# iot_pcb.net
KiCad netlist of a schematic drawn in EAGLE
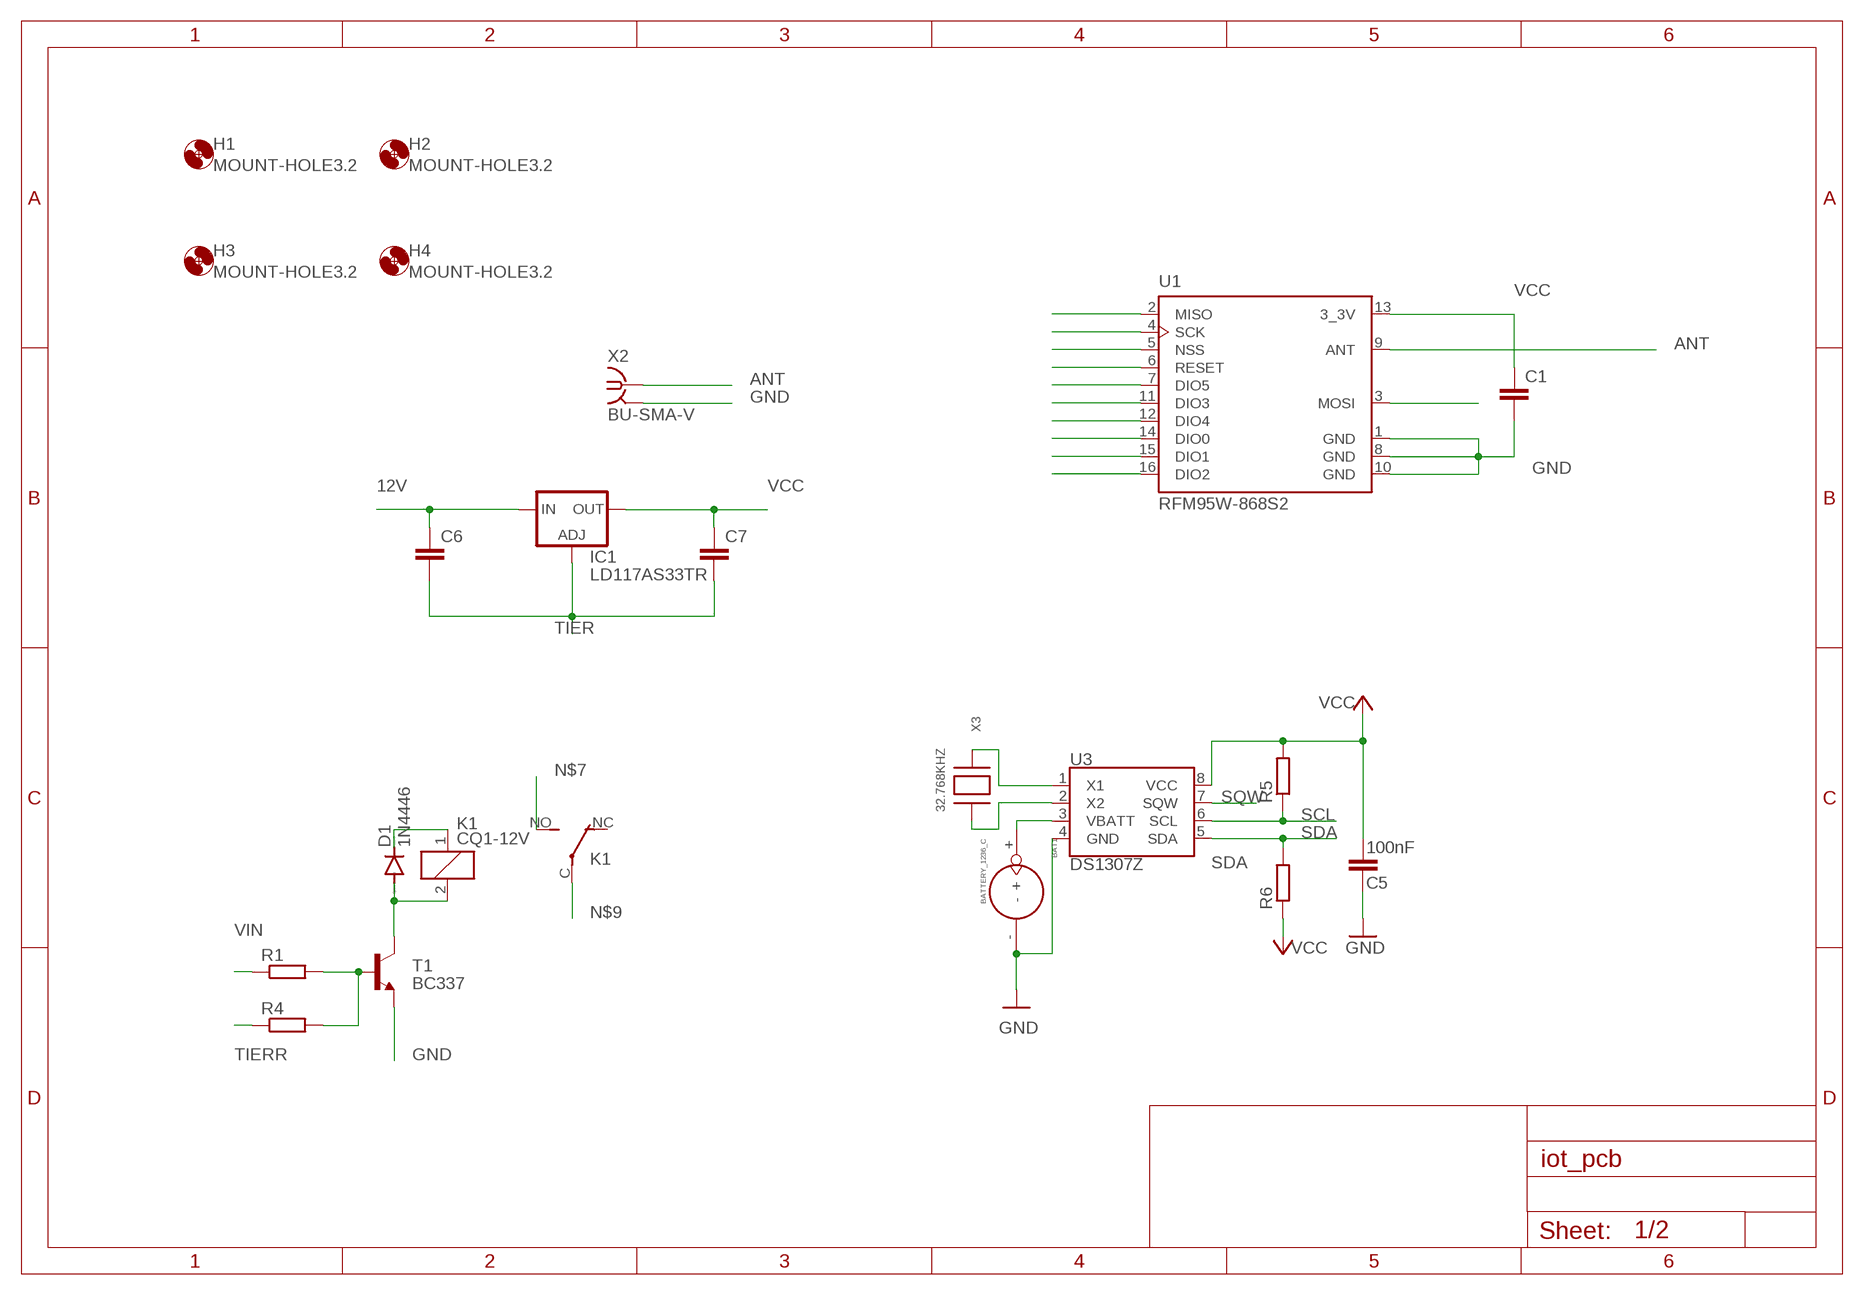
[diagram p0: schematic, sheet 1]
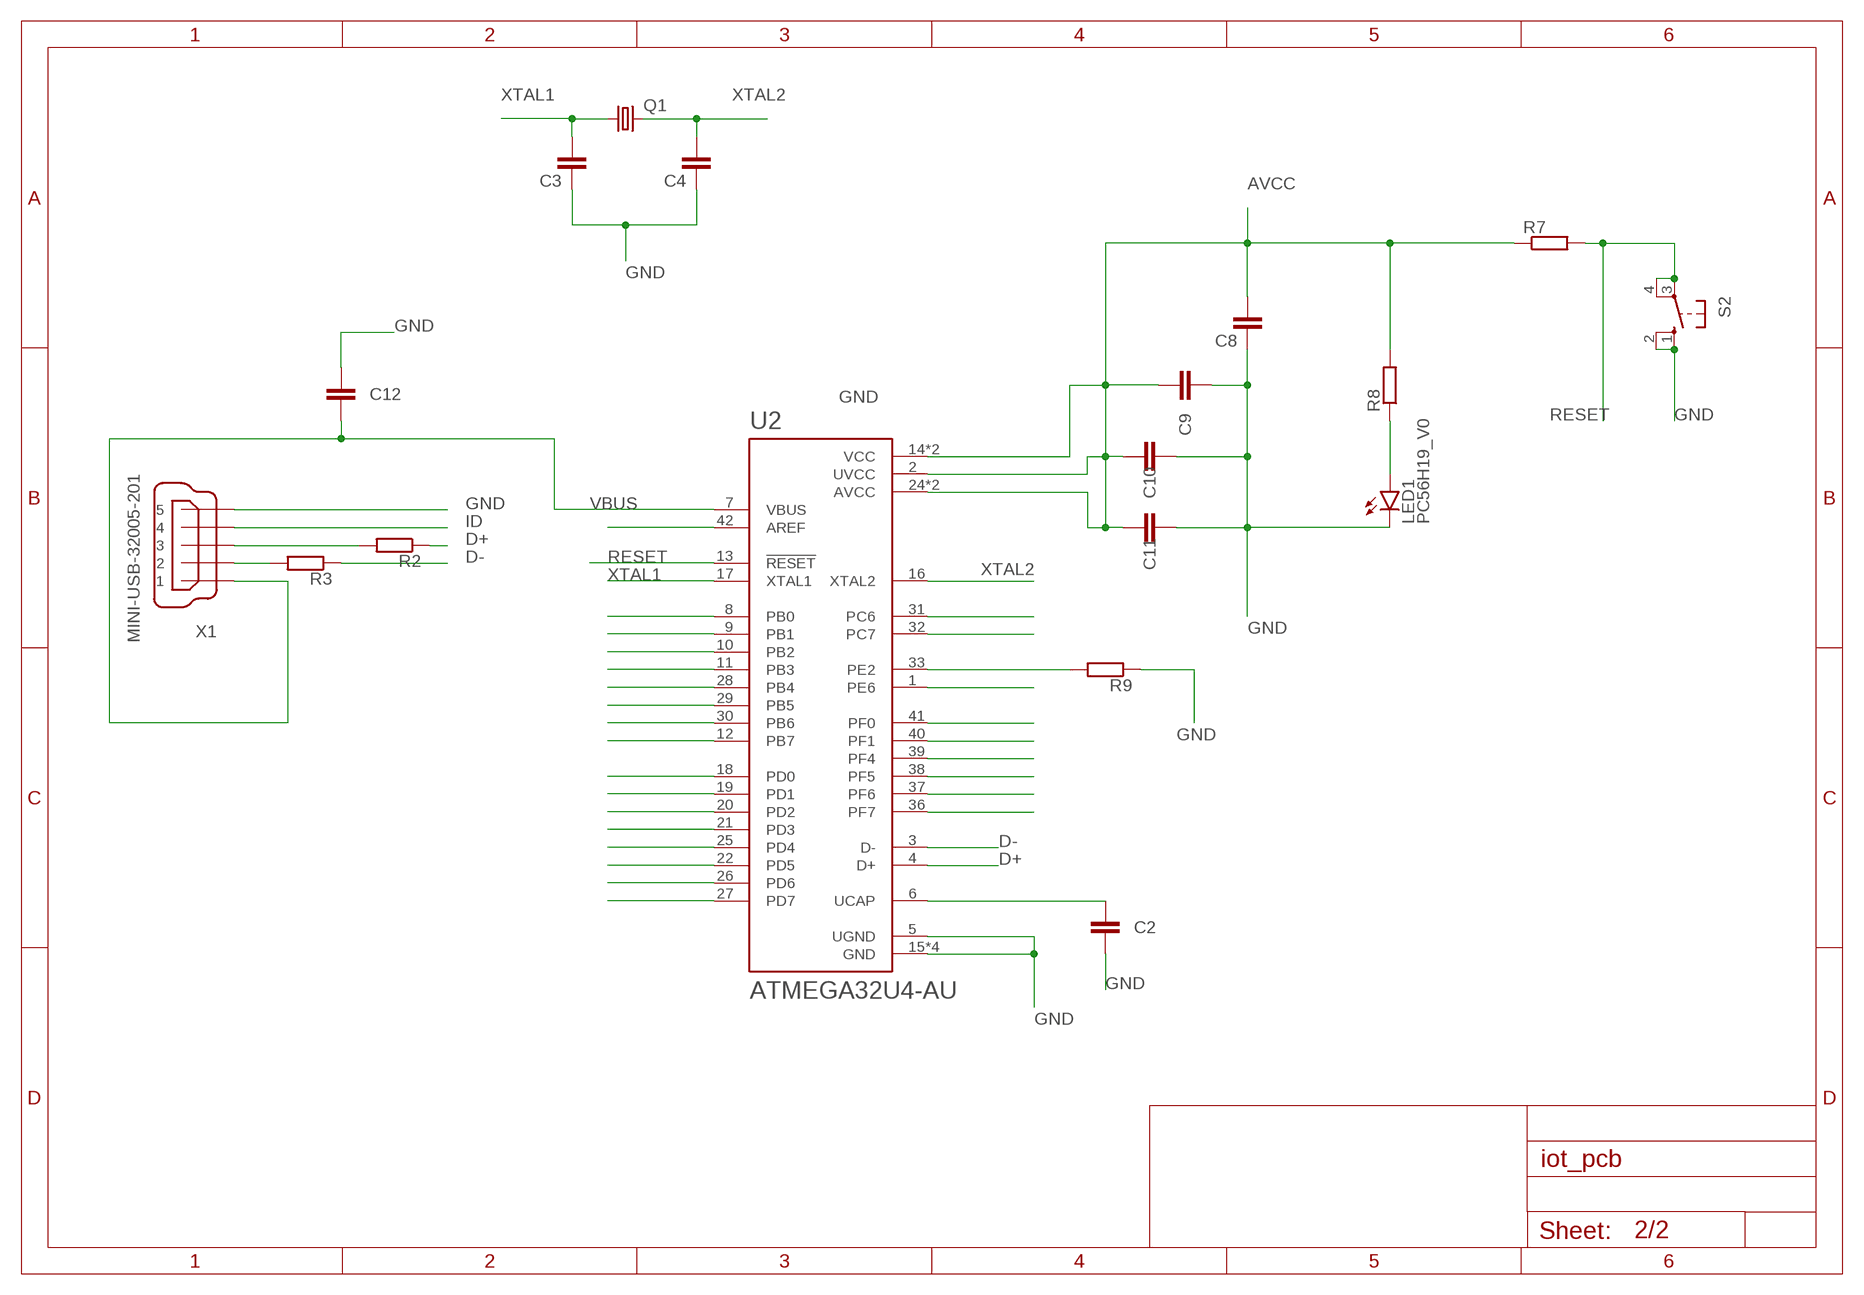
[diagram p1: schematic, sheet 2]

(export (version "E")
  (design (tool "Eeschema 10.0.6"))
  (components
    (comp (ref "BAT1")
      (value "BATTERY_1236_C")
      (footprint "eagle-import:BATTERY_1236_C")
      (libsource (lib "eagle-import") (part "BATTERY_1236_C"))
    )
    (comp (ref "C1")
      (value "C-EU050-025X075")
      (footprint "eagle-import:C050-025X075")
      (libsource (lib "eagle-import") (part "rcl_334_C-EU050-025X075"))
    )
    (comp (ref "C5")
      (value "100nF")
      (footprint "eagle-import:C0603")
      (libsource (lib "eagle-import") (part "C-EUC0603"))
    )
    (comp (ref "C6")
      (value "C-EU050-025X075")
      (footprint "eagle-import:C050-025X075")
      (libsource (lib "eagle-import") (part "rcl_334_C-EU050-025X075"))
    )
    (comp (ref "C7")
      (value "C-EU050-025X075")
      (footprint "eagle-import:C050-025X075")
      (libsource (lib "eagle-import") (part "rcl_334_C-EU050-025X075"))
    )
    (comp (ref "D1")
      (value "1N4446")
      (footprint "eagle-import:DO35-10")
      (libsource (lib "eagle-import") (part "1N4446"))
    )
    (comp (ref "H1")
      (value "MOUNT-HOLE3.2")
      (footprint "eagle-import:3,2")
      (libsource (lib "eagle-import") (part "MOUNT-HOLE3.2"))
    )
    (comp (ref "H2")
      (value "MOUNT-HOLE3.2")
      (footprint "eagle-import:3,2")
      (libsource (lib "eagle-import") (part "MOUNT-HOLE3.2"))
    )
    (comp (ref "H3")
      (value "MOUNT-HOLE3.2")
      (footprint "eagle-import:3,2")
      (libsource (lib "eagle-import") (part "MOUNT-HOLE3.2"))
    )
    (comp (ref "H4")
      (value "MOUNT-HOLE3.2")
      (footprint "eagle-import:3,2")
      (libsource (lib "eagle-import") (part "MOUNT-HOLE3.2"))
    )
    (comp (ref "IC1")
      (value "LD117AS33TR")
      (footprint "eagle-import:SOT223")
      (libsource (lib "eagle-import") (part "LD117A?S33TR"))
    )
    (comp (ref "K1")
      (value "CQ1-12V")
      (footprint "eagle-import:CQ1")
      (libsource (lib "eagle-import") (part "CQ1-12V"))
    )
    (comp (ref "R1")
      (value "R-EU_0207/10")
      (footprint "eagle-import:0207_10")
      (libsource (lib "eagle-import") (part "R-EU_0207/10"))
    )
    (comp (ref "R4")
      (value "R-EU_0207/10")
      (footprint "eagle-import:0207_10")
      (libsource (lib "eagle-import") (part "R-EU_0207/10"))
    )
    (comp (ref "R5")
      (value "R-EU_0207/10")
      (footprint "eagle-import:0207_10")
      (libsource (lib "eagle-import") (part "R-EU_0207/10"))
    )
    (comp (ref "R6")
      (value "R-EU_0207/10")
      (footprint "eagle-import:0207_10")
      (libsource (lib "eagle-import") (part "R-EU_0207/10"))
    )
    (comp (ref "T1")
      (value "BC337")
      (footprint "eagle-import:TO92")
      (libsource (lib "eagle-import") (part "BC337"))
    )
    (comp (ref "U1")
      (value "RFM95W-868S2")
      (footprint "eagle-import:XCVR_RFM95W-868S2")
      (fields (field (name "MF") "RF"))
      (libsource (lib "eagle-import") (part "RFM95W-868S2"))
    )
    (comp (ref "U3")
      (value "DS1307Z")
      (footprint "eagle-import:SO08-0.15")
      (libsource (lib "eagle-import") (part "DS1307Z"))
    )
    (comp (ref "X2")
      (value "BU-SMA-V")
      (footprint "eagle-import:BU-SMA-V")
      (libsource (lib "eagle-import") (part "BU-SMA-V"))
    )
    (comp (ref "X3")
      (value "32.768KHZ")
      (footprint "eagle-import:XTAL3215")
      (libsource (lib "eagle-import") (part "XTAL-3.2X1.5"))
    )
    (comp (ref "C2")
      (value "C-EU050-025X075")
      (footprint "eagle-import:C050-025X075")
      (libsource (lib "eagle-import") (part "rcl_334_C-EU050-025X075"))
    )
    (comp (ref "C3")
      (value "C-EU050-025X075")
      (footprint "eagle-import:C050-025X075")
      (libsource (lib "eagle-import") (part "rcl_334_C-EU050-025X075"))
    )
    (comp (ref "C4")
      (value "C-EU050-025X075")
      (footprint "eagle-import:C050-025X075")
      (libsource (lib "eagle-import") (part "rcl_334_C-EU050-025X075"))
    )
    (comp (ref "C8")
      (value "C-EU050-025X075")
      (footprint "eagle-import:C050-025X075")
      (libsource (lib "eagle-import") (part "rcl_334_C-EU050-025X075"))
    )
    (comp (ref "C9")
      (value "C-EU050-025X075")
      (footprint "eagle-import:C050-025X075")
      (libsource (lib "eagle-import") (part "rcl_334_C-EU050-025X075"))
    )
    (comp (ref "C10")
      (value "C-EU050-025X075")
      (footprint "eagle-import:C050-025X075")
      (libsource (lib "eagle-import") (part "rcl_334_C-EU050-025X075"))
    )
    (comp (ref "C11")
      (value "C-EU050-025X075")
      (footprint "eagle-import:C050-025X075")
      (libsource (lib "eagle-import") (part "rcl_334_C-EU050-025X075"))
    )
    (comp (ref "C12")
      (value "C-EU050-025X075")
      (footprint "eagle-import:C050-025X075")
      (libsource (lib "eagle-import") (part "rcl_334_C-EU050-025X075"))
    )
    (comp (ref "LED1")
      (value "PC56H19_V0")
      (footprint "eagle-import:PC56H19_V0")
      (libsource (lib "eagle-import") (part "PC56H19_V0"))
    )
    (comp (ref "Q1")
      (value "CRYSTALHC49S")
      (footprint "eagle-import:HC49_S")
      (libsource (lib "eagle-import") (part "CRYSTALHC49S"))
    )
    (comp (ref "R2")
      (value "R-EU_0204/7")
      (footprint "eagle-import:0204_7")
      (libsource (lib "eagle-import") (part "R-EU_0204/7"))
    )
    (comp (ref "R3")
      (value "R-EU_0204/7")
      (footprint "eagle-import:0204_7")
      (libsource (lib "eagle-import") (part "R-EU_0204/7"))
    )
    (comp (ref "R7")
      (value "R-EU_0204/7")
      (footprint "eagle-import:0204_7")
      (libsource (lib "eagle-import") (part "R-EU_0204/7"))
    )
    (comp (ref "R8")
      (value "R-EU_0204/7")
      (footprint "eagle-import:0204_7")
      (libsource (lib "eagle-import") (part "R-EU_0204/7"))
    )
    (comp (ref "R9")
      (value "R-EU_0204/7")
      (footprint "eagle-import:0204_7")
      (libsource (lib "eagle-import") (part "R-EU_0204/7"))
    )
    (comp (ref "S2")
      (value "40-XX")
      (footprint "eagle-import:B3F-40XX")
      (fields (field (name "MF") "OMRON COMPONENTS USA") (field (name "MPN") "B3F-4000"))
      (libsource (lib "eagle-import") (part "40-XX"))
    )
    (comp (ref "U2")
      (value "ATMEGA32U4-AU")
      (footprint "eagle-import:QFP80P1200X1200X120-44N")
      (fields (field (name "MF") "Rochester Electronics, LLC"))
      (libsource (lib "eagle-import") (part "ATMEGA32U4-AU"))
    )
    (comp (ref "X1")
      (value "MINI-USB-32005-201")
      (footprint "eagle-import:32005-201")
      (libsource (lib "eagle-import") (part "MINI-USB-32005-201"))
    )
  )
  (nets
    (net (code "1") (name "12V") (class "Default")
      (node (ref "C6") (pin "1") (pinfunction "1_1") (pintype "passive"))
      (node (ref "IC1") (pin "3") (pinfunction "IN_3") (pintype "input"))
    )
    (net (code "2") (name "ANT") (class "Default")
      (node (ref "U1") (pin "9") (pinfunction "ANT_9") (pintype "passive"))
      (node (ref "X2") (pin "1") (pinfunction "1_1") (pintype "passive"))
    )
    (net (code "3") (name "AVCC") (class "Default")
      (node (ref "C10") (pin "2") (pinfunction "2_2") (pintype "passive"))
      (node (ref "C11") (pin "1") (pinfunction "1_1") (pintype "passive"))
      (node (ref "C8") (pin "2") (pinfunction "2_2") (pintype "passive"))
      (node (ref "C9") (pin "2") (pinfunction "2_2") (pintype "passive"))
      (node (ref "R7") (pin "1") (pinfunction "1_1") (pintype "passive"))
      (node (ref "R8") (pin "2") (pinfunction "2_2") (pintype "passive"))
      (node (ref "U2") (pin "14") (pinfunction "VCC_14") (pintype "power_in"))
      (node (ref "U2") (pin "2") (pinfunction "UVCC_2") (pintype "power_in"))
      (node (ref "U2") (pin "24") (pinfunction "AVCC_24") (pintype "power_in"))
      (node (ref "U2") (pin "34") (pinfunction "VCC_34") (pintype "power_in"))
      (node (ref "U2") (pin "44") (pinfunction "AVCC_44") (pintype "power_in"))
    )
    (net (code "4") (name "D+") (class "Default")
      (node (ref "R2") (pin "1") (pinfunction "1_1") (pintype "passive"))
      (node (ref "U2") (pin "4") (pinfunction "D+_4") (pintype "bidirectional"))
    )
    (net (code "5") (name "D-") (class "Default")
      (node (ref "R3") (pin "1") (pinfunction "1_1") (pintype "passive"))
      (node (ref "U2") (pin "3") (pinfunction "D-_3") (pintype "bidirectional"))
    )
    (net (code "6") (name "GND") (class "Default")
      (node (ref "BAT1") (pin "-") (pinfunction "-_-") (pintype "bidirectional"))
      (node (ref "C1") (pin "2") (pinfunction "2_2") (pintype "passive"))
      (node (ref "C10") (pin "1") (pinfunction "1_1") (pintype "passive"))
      (node (ref "C11") (pin "2") (pinfunction "2_2") (pintype "passive"))
      (node (ref "C12") (pin "1") (pinfunction "1_1") (pintype "passive"))
      (node (ref "C2") (pin "2") (pinfunction "2_2") (pintype "passive"))
      (node (ref "C3") (pin "1") (pinfunction "1_1") (pintype "passive"))
      (node (ref "C4") (pin "1") (pinfunction "1_1") (pintype "passive"))
      (node (ref "C5") (pin "1") (pinfunction "1_1") (pintype "passive"))
      (node (ref "C8") (pin "1") (pinfunction "1_1") (pintype "passive"))
      (node (ref "C9") (pin "1") (pinfunction "1_1") (pintype "passive"))
      (node (ref "LED1") (pin "1") (pinfunction "C_1") (pintype "passive"))
      (node (ref "LED1") (pin "3") (pinfunction "C_3") (pintype "passive"))
      (node (ref "R9") (pin "1") (pinfunction "1_1") (pintype "passive"))
      (node (ref "S2") (pin "1") (pinfunction "S_1") (pintype "passive"))
      (node (ref "S2") (pin "2") (pinfunction "S1_2") (pintype "passive"))
      (node (ref "T1") (pin "1") (pinfunction "E_1") (pintype "passive"))
      (node (ref "U1") (pin "1") (pinfunction "GND_1") (pintype "power_in"))
      (node (ref "U1") (pin "10") (pinfunction "GND_10") (pintype "power_in"))
      (node (ref "U1") (pin "8") (pinfunction "GND_8") (pintype "power_in"))
      (node (ref "U2") (pin "15") (pinfunction "GND_15") (pintype "power_in"))
      (node (ref "U2") (pin "23") (pinfunction "GND_23") (pintype "power_in"))
      (node (ref "U2") (pin "35") (pinfunction "GND_35") (pintype "power_in"))
      (node (ref "U2") (pin "43") (pinfunction "GND_43") (pintype "power_in"))
      (node (ref "U2") (pin "5") (pinfunction "UGND_5") (pintype "power_in"))
      (node (ref "U3") (pin "4") (pinfunction "GND_4") (pintype "bidirectional"))
      (node (ref "X1") (pin "5") (pinfunction "5_5") (pintype "passive"))
      (node (ref "X2") (pin "2") (pinfunction "2_2") (pintype "passive"))
      (node (ref "X2") (pin "3") (pinfunction "2_3") (pintype "passive"))
      (node (ref "X2") (pin "4") (pinfunction "2_4") (pintype "passive"))
      (node (ref "X2") (pin "5") (pinfunction "2_5") (pintype "passive"))
    )
    (net (code "7") (name "ID") (class "Default")
      (node (ref "X1") (pin "4") (pinfunction "4_4") (pintype "passive"))
    )
    (net (code "8") (name "N$7") (class "Default")
      (node (ref "K1") (pin "NO") (pinfunction "S_NO") (pintype "passive"))
      (node (ref "U2") (pin "10") (pinfunction "PB2_10") (pintype "bidirectional"))
    )
    (net (code "9") (name "N$9") (class "Default")
      (node (ref "K1") (pin "C") (pinfunction "P_C") (pintype "passive"))
      (node (ref "U2") (pin "28") (pinfunction "PB4_28") (pintype "bidirectional"))
    )
    (net (code "10") (name "Net-(D1-PadC)") (class "Default")
      (node (ref "D1") (pin "C") (pinfunction "C_C") (pintype "passive"))
      (node (ref "K1") (pin "1") (pinfunction "1_1") (pintype "passive"))
    )
    (net (code "11") (name "Net-(LED1-A-Pad2)") (class "Default")
      (node (ref "LED1") (pin "2") (pinfunction "A_2") (pintype "passive"))
      (node (ref "LED1") (pin "4") (pinfunction "A_4") (pintype "passive"))
      (node (ref "R8") (pin "1") (pinfunction "1_1") (pintype "passive"))
    )
    (net (code "12") (name "Net-(R2-Pad2)") (class "Default")
      (node (ref "R2") (pin "2") (pinfunction "2_2") (pintype "passive"))
      (node (ref "X1") (pin "3") (pinfunction "3_3") (pintype "passive"))
    )
    (net (code "13") (name "Net-(R3-Pad2)") (class "Default")
      (node (ref "R3") (pin "2") (pinfunction "2_2") (pintype "passive"))
      (node (ref "X1") (pin "2") (pinfunction "2_2") (pintype "passive"))
    )
    (net (code "14") (name "Net-(T1-B)") (class "Default")
      (node (ref "R1") (pin "2") (pinfunction "2_2") (pintype "passive"))
      (node (ref "R4") (pin "2") (pinfunction "2_2") (pintype "passive"))
      (node (ref "T1") (pin "2") (pinfunction "B_2") (pintype "passive"))
    )
    (net (code "15") (name "Net-(T1-C)") (class "Default")
      (node (ref "D1") (pin "A") (pinfunction "A_A") (pintype "passive"))
      (node (ref "K1") (pin "2") (pinfunction "2_2") (pintype "passive"))
      (node (ref "T1") (pin "3") (pinfunction "C_3") (pintype "passive"))
    )
    (net (code "16") (name "Net-(U2-PE2)") (class "Default")
      (node (ref "R9") (pin "2") (pinfunction "2_2") (pintype "passive"))
      (node (ref "U2") (pin "33") (pinfunction "PE2_33") (pintype "bidirectional"))
    )
    (net (code "17") (name "Net-(U2-UCAP)") (class "Default")
      (node (ref "C2") (pin "1") (pinfunction "1_1") (pintype "passive"))
      (node (ref "U2") (pin "6") (pinfunction "UCAP_6") (pintype "passive"))
    )
    (net (code "18") (name "Net-(U3-VBATT)") (class "Default")
      (node (ref "BAT1") (pin "+") (pinfunction "+_+") (pintype "bidirectional"))
      (node (ref "U3") (pin "3") (pinfunction "VBATT_3") (pintype "bidirectional"))
    )
    (net (code "19") (name "Net-(U3-X1)") (class "Default")
      (node (ref "U3") (pin "1") (pinfunction "X1_1") (pintype "bidirectional"))
      (node (ref "X3") (pin "P$2") (pinfunction "P$2_P$2") (pintype "bidirectional"))
    )
    (net (code "20") (name "Net-(U3-X2)") (class "Default")
      (node (ref "U3") (pin "2") (pinfunction "X2_2") (pintype "bidirectional"))
      (node (ref "X3") (pin "P$1") (pinfunction "P$1_P$1") (pintype "bidirectional"))
    )
    (net (code "21") (name "RESET") (class "Default")
      (node (ref "R7") (pin "2") (pinfunction "2_2") (pintype "passive"))
      (node (ref "S2") (pin "3") (pinfunction "P_3") (pintype "passive"))
      (node (ref "S2") (pin "4") (pinfunction "P1_4") (pintype "passive"))
      (node (ref "U2") (pin "13") (pinfunction "~{RESET}_13") (pintype "input"))
    )
    (net (code "22") (name "SCL") (class "Default")
      (node (ref "R5") (pin "1") (pinfunction "1_1") (pintype "passive"))
      (node (ref "U3") (pin "6") (pinfunction "SCL_6") (pintype "bidirectional"))
    )
    (net (code "23") (name "SDA") (class "Default")
      (node (ref "R6") (pin "2") (pinfunction "2_2") (pintype "passive"))
      (node (ref "U3") (pin "5") (pinfunction "SDA_5") (pintype "bidirectional"))
    )
    (net (code "24") (name "SQW") (class "Default")
      (node (ref "U3") (pin "7") (pinfunction "SQW_7") (pintype "bidirectional"))
    )
    (net (code "25") (name "TIER") (class "Default")
      (node (ref "C6") (pin "2") (pinfunction "2_2") (pintype "passive"))
      (node (ref "C7") (pin "2") (pinfunction "2_2") (pintype "passive"))
      (node (ref "IC1") (pin "1") (pinfunction "ADJ_1") (pintype "input"))
    )
    (net (code "26") (name "TIERR") (class "Default")
      (node (ref "R4") (pin "1") (pinfunction "1_1") (pintype "passive"))
    )
    (net (code "27") (name "VBUS") (class "Default")
      (node (ref "C12") (pin "2") (pinfunction "2_2") (pintype "passive"))
      (node (ref "U2") (pin "7") (pinfunction "VBUS_7") (pintype "input"))
      (node (ref "X1") (pin "1") (pinfunction "1_1") (pintype "passive"))
    )
    (net (code "28") (name "VCC") (class "Default")
      (node (ref "C1") (pin "1") (pinfunction "1_1") (pintype "passive"))
      (node (ref "C5") (pin "2") (pinfunction "2_2") (pintype "passive"))
      (node (ref "C7") (pin "1") (pinfunction "1_1") (pintype "passive"))
      (node (ref "IC1") (pin "4") (pinfunction "OUT_4") (pintype "passive"))
      (node (ref "R5") (pin "2") (pinfunction "2_2") (pintype "passive"))
      (node (ref "R6") (pin "1") (pinfunction "1_1") (pintype "passive"))
      (node (ref "U1") (pin "13") (pinfunction "3_3V_13") (pintype "power_in"))
      (node (ref "U3") (pin "8") (pinfunction "VCC_8") (pintype "bidirectional"))
    )
    (net (code "29") (name "VIN") (class "Default")
      (node (ref "R1") (pin "1") (pinfunction "1_1") (pintype "passive"))
    )
    (net (code "30") (name "XTAL1") (class "Default")
      (node (ref "C3") (pin "2") (pinfunction "2_2") (pintype "passive"))
      (node (ref "Q1") (pin "1") (pinfunction "1_1") (pintype "passive"))
      (node (ref "U2") (pin "17") (pinfunction "XTAL1_17") (pintype "input"))
    )
    (net (code "31") (name "XTAL2") (class "Default")
      (node (ref "C4") (pin "2") (pinfunction "2_2") (pintype "passive"))
      (node (ref "Q1") (pin "2") (pinfunction "2_2") (pintype "passive"))
      (node (ref "U2") (pin "16") (pinfunction "XTAL2_16") (pintype "output"))
    )
    (net (code "32") (name "unconnected-(K1B-O-PadNC)") (class "Default")
      (node (ref "K1") (pin "NC") (pinfunction "O_NC") (pintype "passive"))
    )
    (net (code "33") (name "unconnected-(U1-DIO0-Pad14)") (class "Default")
      (node (ref "U1") (pin "14") (pinfunction "DIO0_14") (pintype "bidirectional"))
    )
    (net (code "34") (name "unconnected-(U1-DIO1-Pad15)") (class "Default")
      (node (ref "U1") (pin "15") (pinfunction "DIO1_15") (pintype "bidirectional"))
    )
    (net (code "35") (name "unconnected-(U1-DIO2-Pad16)") (class "Default")
      (node (ref "U1") (pin "16") (pinfunction "DIO2_16") (pintype "bidirectional"))
    )
    (net (code "36") (name "unconnected-(U1-DIO3-Pad11)") (class "Default")
      (node (ref "U1") (pin "11") (pinfunction "DIO3_11") (pintype "bidirectional"))
    )
    (net (code "37") (name "unconnected-(U1-DIO4-Pad12)") (class "Default")
      (node (ref "U1") (pin "12") (pinfunction "DIO4_12") (pintype "bidirectional"))
    )
    (net (code "38") (name "unconnected-(U1-DIO5-Pad7)") (class "Default")
      (node (ref "U1") (pin "7") (pinfunction "DIO5_7") (pintype "bidirectional"))
    )
    (net (code "39") (name "unconnected-(U1-MISO-Pad2)") (class "Default")
      (node (ref "U1") (pin "2") (pinfunction "MISO_2") (pintype "input"))
    )
    (net (code "40") (name "unconnected-(U1-MOSI-Pad3)") (class "Default")
      (node (ref "U1") (pin "3") (pinfunction "MOSI_3") (pintype "output"))
    )
    (net (code "41") (name "unconnected-(U1-NSS-Pad5)") (class "Default")
      (node (ref "U1") (pin "5") (pinfunction "NSS_5") (pintype "input"))
    )
    (net (code "42") (name "unconnected-(U1-RESET-Pad6)") (class "Default")
      (node (ref "U1") (pin "6") (pinfunction "RESET_6") (pintype "bidirectional"))
    )
    (net (code "43") (name "unconnected-(U1-SCK-Pad4)") (class "Default")
      (node (ref "U1") (pin "4") (pinfunction "SCK_4") (pintype "input"))
    )
    (net (code "44") (name "unconnected-(U2-AREF-Pad42)") (class "Default")
      (node (ref "U2") (pin "42") (pinfunction "AREF_42") (pintype "input"))
    )
    (net (code "45") (name "unconnected-(U2-PB0-Pad8)") (class "Default")
      (node (ref "U2") (pin "8") (pinfunction "PB0_8") (pintype "bidirectional"))
    )
    (net (code "46") (name "unconnected-(U2-PB1-Pad9)") (class "Default")
      (node (ref "U2") (pin "9") (pinfunction "PB1_9") (pintype "bidirectional"))
    )
    (net (code "47") (name "unconnected-(U2-PB3-Pad11)") (class "Default")
      (node (ref "U2") (pin "11") (pinfunction "PB3_11") (pintype "bidirectional"))
    )
    (net (code "48") (name "unconnected-(U2-PB5-Pad29)") (class "Default")
      (node (ref "U2") (pin "29") (pinfunction "PB5_29") (pintype "bidirectional"))
    )
    (net (code "49") (name "unconnected-(U2-PB6-Pad30)") (class "Default")
      (node (ref "U2") (pin "30") (pinfunction "PB6_30") (pintype "bidirectional"))
    )
    (net (code "50") (name "unconnected-(U2-PB7-Pad12)") (class "Default")
      (node (ref "U2") (pin "12") (pinfunction "PB7_12") (pintype "bidirectional"))
    )
    (net (code "51") (name "unconnected-(U2-PC6-Pad31)") (class "Default")
      (node (ref "U2") (pin "31") (pinfunction "PC6_31") (pintype "bidirectional"))
    )
    (net (code "52") (name "unconnected-(U2-PC7-Pad32)") (class "Default")
      (node (ref "U2") (pin "32") (pinfunction "PC7_32") (pintype "bidirectional"))
    )
    (net (code "53") (name "unconnected-(U2-PD0-Pad18)") (class "Default")
      (node (ref "U2") (pin "18") (pinfunction "PD0_18") (pintype "bidirectional"))
    )
    (net (code "54") (name "unconnected-(U2-PD1-Pad19)") (class "Default")
      (node (ref "U2") (pin "19") (pinfunction "PD1_19") (pintype "bidirectional"))
    )
    (net (code "55") (name "unconnected-(U2-PD2-Pad20)") (class "Default")
      (node (ref "U2") (pin "20") (pinfunction "PD2_20") (pintype "bidirectional"))
    )
    (net (code "56") (name "unconnected-(U2-PD3-Pad21)") (class "Default")
      (node (ref "U2") (pin "21") (pinfunction "PD3_21") (pintype "bidirectional"))
    )
    (net (code "57") (name "unconnected-(U2-PD4-Pad25)") (class "Default")
      (node (ref "U2") (pin "25") (pinfunction "PD4_25") (pintype "bidirectional"))
    )
    (net (code "58") (name "unconnected-(U2-PD5-Pad22)") (class "Default")
      (node (ref "U2") (pin "22") (pinfunction "PD5_22") (pintype "bidirectional"))
    )
    (net (code "59") (name "unconnected-(U2-PD6-Pad26)") (class "Default")
      (node (ref "U2") (pin "26") (pinfunction "PD6_26") (pintype "bidirectional"))
    )
    (net (code "60") (name "unconnected-(U2-PD7-Pad27)") (class "Default")
      (node (ref "U2") (pin "27") (pinfunction "PD7_27") (pintype "bidirectional"))
    )
    (net (code "61") (name "unconnected-(U2-PE6-Pad1)") (class "Default")
      (node (ref "U2") (pin "1") (pinfunction "PE6_1") (pintype "bidirectional"))
    )
    (net (code "62") (name "unconnected-(U2-PF0-Pad41)") (class "Default")
      (node (ref "U2") (pin "41") (pinfunction "PF0_41") (pintype "bidirectional"))
    )
    (net (code "63") (name "unconnected-(U2-PF1-Pad40)") (class "Default")
      (node (ref "U2") (pin "40") (pinfunction "PF1_40") (pintype "bidirectional"))
    )
    (net (code "64") (name "unconnected-(U2-PF4-Pad39)") (class "Default")
      (node (ref "U2") (pin "39") (pinfunction "PF4_39") (pintype "bidirectional"))
    )
    (net (code "65") (name "unconnected-(U2-PF5-Pad38)") (class "Default")
      (node (ref "U2") (pin "38") (pinfunction "PF5_38") (pintype "bidirectional"))
    )
    (net (code "66") (name "unconnected-(U2-PF6-Pad37)") (class "Default")
      (node (ref "U2") (pin "37") (pinfunction "PF6_37") (pintype "bidirectional"))
    )
    (net (code "67") (name "unconnected-(U2-PF7-Pad36)") (class "Default")
      (node (ref "U2") (pin "36") (pinfunction "PF7_36") (pintype "bidirectional"))
    )
  )
)
